# esp8255-full-breakout.net
KiCad netlist of a schematic drawn in EAGLE
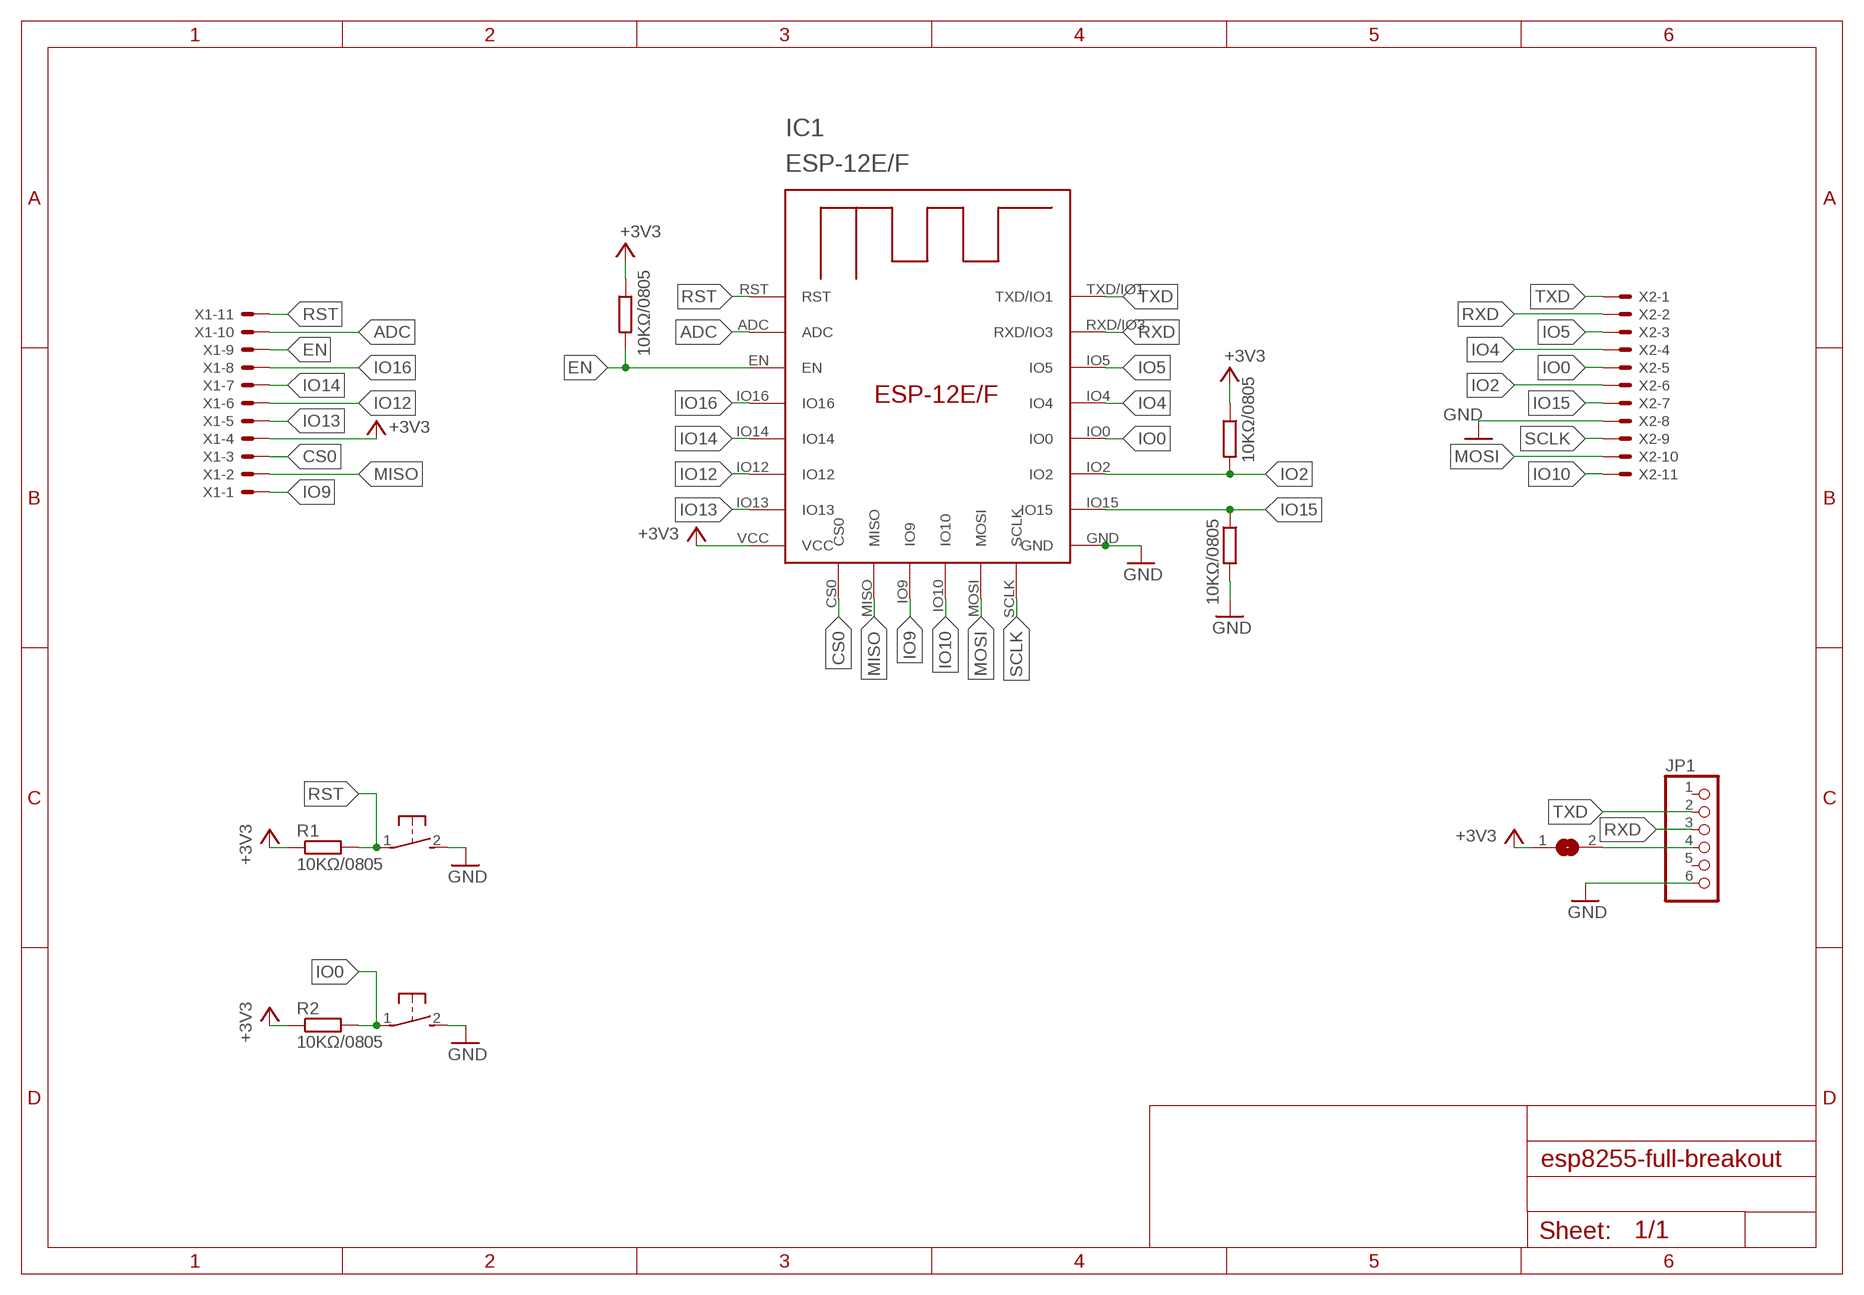
[diagram p0: schematic, sheet 1]

(export (version "E")
  (design (tool "Eeschema 10.0.6"))
  (components
    (comp (ref "IC1")
      (value "ESP-12E/F")
      (footprint "eagle-import:ESP-12E")
      (libsource (lib "eagle-import") (part "ESP-12E/F"))
    )
    (comp (ref "JP1")
      (value "PINHD-1X6B")
      (footprint "eagle-import:1X06-BIG")
      (libsource (lib "eagle-import") (part "PINHD-1X6B"))
    )
    (comp (ref "R1")
      (value "10KΩ/0805")
      (footprint "eagle-import:R0805")
      (libsource (lib "eagle-import") (part "R-EU_R0805"))
    )
    (comp (ref "R2")
      (value "10KΩ/0805")
      (footprint "eagle-import:R0805")
      (libsource (lib "eagle-import") (part "R-EU_R0805"))
    )
    (comp (ref "R3")
      (value "10KΩ/0805")
      (footprint "eagle-import:R0805")
      (libsource (lib "eagle-import") (part "R-EU_R0805"))
    )
    (comp (ref "R4")
      (value "10KΩ/0805")
      (footprint "eagle-import:R0805")
      (libsource (lib "eagle-import") (part "R-EU_R0805"))
    )
    (comp (ref "R5")
      (value "10KΩ/0805")
      (footprint "eagle-import:R0805")
      (libsource (lib "eagle-import") (part "R-EU_R0805"))
    )
    (comp (ref "S1")
      (value "DTSM-3")
      (footprint "eagle-import:DTSM-3")
      (libsource (lib "eagle-import") (part "DTSM-3"))
    )
    (comp (ref "S2")
      (value "DTSM-3")
      (footprint "eagle-import:DTSM-3")
      (libsource (lib "eagle-import") (part "DTSM-3"))
    )
    (comp (ref "SJ1") (value "SJ") (footprint "eagle-import:SJ") (libsource (lib "eagle-import") (part "SJ")))
    (comp (ref "X1")
      (value "JST-XH-11-PIN-ROUND-PAD")
      (footprint "eagle-import:JST-XH-11-PACKAGE-ROUND-PAD")
      (libsource (lib "eagle-import") (part "JST-XH-11-PIN-ROUND-PAD"))
    )
    (comp (ref "X2")
      (value "JST-XH-11-PIN-ROUND-PAD")
      (footprint "eagle-import:JST-XH-11-PACKAGE-ROUND-PAD")
      (libsource (lib "eagle-import") (part "JST-XH-11-PIN-ROUND-PAD"))
    )
  )
  (nets
    (net (code "1") (name "+3V3") (class "Default")
      (node (ref "IC1") (pin "VCC") (pinfunction "VCC_VCC") (pintype "power_in"))
      (node (ref "R1") (pin "1") (pinfunction "1_1") (pintype "passive"))
      (node (ref "R2") (pin "1") (pinfunction "1_1") (pintype "passive"))
      (node (ref "R4") (pin "1") (pinfunction "1_1") (pintype "passive"))
      (node (ref "R5") (pin "1") (pinfunction "1_1") (pintype "passive"))
      (node (ref "SJ1") (pin "1") (pinfunction "1_1") (pintype "passive"))
      (node (ref "X1") (pin "4") (pinfunction "S_4") (pintype "passive"))
    )
    (net (code "2") (name "ADC") (class "Default")
      (node (ref "IC1") (pin "ADC") (pinfunction "ADC_ADC") (pintype "bidirectional"))
      (node (ref "X1") (pin "10") (pinfunction "S_10") (pintype "passive"))
    )
    (net (code "3") (name "CS0") (class "Default")
      (node (ref "IC1") (pin "CS0") (pinfunction "CS0_CS0") (pintype "bidirectional"))
      (node (ref "X1") (pin "3") (pinfunction "S_3") (pintype "passive"))
    )
    (net (code "4") (name "EN") (class "Default")
      (node (ref "IC1") (pin "EN") (pinfunction "EN_EN") (pintype "bidirectional"))
      (node (ref "R5") (pin "2") (pinfunction "2_2") (pintype "passive"))
      (node (ref "X1") (pin "9") (pinfunction "S_9") (pintype "passive"))
    )
    (net (code "5") (name "GND") (class "Default")
      (node (ref "IC1") (pin "GND") (pinfunction "GND_GND") (pintype "power_in"))
      (node (ref "JP1") (pin "6") (pinfunction "6_6") (pintype "passive"))
      (node (ref "R3") (pin "2") (pinfunction "2_2") (pintype "passive"))
      (node (ref "S1") (pin "2") (pinfunction "2_2") (pintype "passive"))
      (node (ref "S2") (pin "2") (pinfunction "2_2") (pintype "passive"))
      (node (ref "X2") (pin "8") (pinfunction "S_8") (pintype "passive"))
    )
    (net (code "6") (name "IO0") (class "Default")
      (node (ref "IC1") (pin "IO0") (pinfunction "IO0_IO0") (pintype "bidirectional"))
      (node (ref "R2") (pin "2") (pinfunction "2_2") (pintype "passive"))
      (node (ref "S2") (pin "1") (pinfunction "1_1") (pintype "passive"))
      (node (ref "X2") (pin "5") (pinfunction "S_5") (pintype "passive"))
    )
    (net (code "7") (name "IO2") (class "Default")
      (node (ref "IC1") (pin "IO2") (pinfunction "IO2_IO2") (pintype "bidirectional"))
      (node (ref "R4") (pin "2") (pinfunction "2_2") (pintype "passive"))
      (node (ref "X2") (pin "6") (pinfunction "S_6") (pintype "passive"))
    )
    (net (code "8") (name "IO4") (class "Default")
      (node (ref "IC1") (pin "IO4") (pinfunction "IO4_IO4") (pintype "bidirectional"))
      (node (ref "X2") (pin "4") (pinfunction "S_4") (pintype "passive"))
    )
    (net (code "9") (name "IO5") (class "Default")
      (node (ref "IC1") (pin "IO5") (pinfunction "IO5_IO5") (pintype "bidirectional"))
      (node (ref "X2") (pin "3") (pinfunction "S_3") (pintype "passive"))
    )
    (net (code "10") (name "IO9") (class "Default")
      (node (ref "IC1") (pin "IO9") (pinfunction "IO9_IO9") (pintype "bidirectional"))
      (node (ref "X1") (pin "1") (pinfunction "S_1") (pintype "passive"))
    )
    (net (code "11") (name "IO10") (class "Default")
      (node (ref "IC1") (pin "IO10") (pinfunction "IO10_IO10") (pintype "bidirectional"))
      (node (ref "X2") (pin "11") (pinfunction "S_11") (pintype "passive"))
    )
    (net (code "12") (name "IO12") (class "Default")
      (node (ref "IC1") (pin "IO12") (pinfunction "IO12_IO12") (pintype "bidirectional"))
      (node (ref "X1") (pin "6") (pinfunction "S_6") (pintype "passive"))
    )
    (net (code "13") (name "IO13") (class "Default")
      (node (ref "IC1") (pin "IO13") (pinfunction "IO13_IO13") (pintype "bidirectional"))
      (node (ref "X1") (pin "5") (pinfunction "S_5") (pintype "passive"))
    )
    (net (code "14") (name "IO14") (class "Default")
      (node (ref "IC1") (pin "IO14") (pinfunction "IO14_IO14") (pintype "bidirectional"))
      (node (ref "X1") (pin "7") (pinfunction "S_7") (pintype "passive"))
    )
    (net (code "15") (name "IO15") (class "Default")
      (node (ref "IC1") (pin "IO15") (pinfunction "IO15_IO15") (pintype "bidirectional"))
      (node (ref "R3") (pin "1") (pinfunction "1_1") (pintype "passive"))
      (node (ref "X2") (pin "7") (pinfunction "S_7") (pintype "passive"))
    )
    (net (code "16") (name "IO16") (class "Default")
      (node (ref "IC1") (pin "IO16") (pinfunction "IO16_IO16") (pintype "bidirectional"))
      (node (ref "X1") (pin "8") (pinfunction "S_8") (pintype "passive"))
    )
    (net (code "17") (name "MISO") (class "Default")
      (node (ref "IC1") (pin "MISO") (pinfunction "MISO_MISO") (pintype "bidirectional"))
      (node (ref "X1") (pin "2") (pinfunction "S_2") (pintype "passive"))
    )
    (net (code "18") (name "MOSI") (class "Default")
      (node (ref "IC1") (pin "MOSI") (pinfunction "MOSI_MOSI") (pintype "bidirectional"))
      (node (ref "X2") (pin "10") (pinfunction "S_10") (pintype "passive"))
    )
    (net (code "19") (name "Net-(JP1-Pad4)") (class "Default")
      (node (ref "JP1") (pin "4") (pinfunction "4_4") (pintype "passive"))
      (node (ref "SJ1") (pin "2") (pinfunction "2_2") (pintype "passive"))
    )
    (net (code "20") (name "RST") (class "Default")
      (node (ref "IC1") (pin "RST") (pinfunction "RST_RST") (pintype "input"))
      (node (ref "R1") (pin "2") (pinfunction "2_2") (pintype "passive"))
      (node (ref "S1") (pin "1") (pinfunction "1_1") (pintype "passive"))
      (node (ref "X1") (pin "11") (pinfunction "S_11") (pintype "passive"))
    )
    (net (code "21") (name "RXD") (class "Default")
      (node (ref "IC1") (pin "RXD/IO3") (pinfunction "RXD/IO3_RXD/IO3") (pintype "bidirectional"))
      (node (ref "JP1") (pin "3") (pinfunction "3_3") (pintype "passive"))
      (node (ref "X2") (pin "2") (pinfunction "S_2") (pintype "passive"))
    )
    (net (code "22") (name "SCLK") (class "Default")
      (node (ref "IC1") (pin "SCLK") (pinfunction "SCLK_SCLK") (pintype "bidirectional"))
      (node (ref "X2") (pin "9") (pinfunction "S_9") (pintype "passive"))
    )
    (net (code "23") (name "TXD") (class "Default")
      (node (ref "IC1") (pin "TXD/IO1") (pinfunction "TXD/IO1_TXD/IO1") (pintype "bidirectional"))
      (node (ref "JP1") (pin "2") (pinfunction "2_2") (pintype "passive"))
      (node (ref "X2") (pin "1") (pinfunction "S_1") (pintype "passive"))
    )
    (net (code "24") (name "unconnected-(JP1-Pad1)") (class "Default")
      (node (ref "JP1") (pin "1") (pinfunction "1_1") (pintype "passive"))
    )
    (net (code "25") (name "unconnected-(JP1-Pad5)") (class "Default")
      (node (ref "JP1") (pin "5") (pinfunction "5_5") (pintype "passive"))
    )
  )
)
